# Tiny_5_Stick_PTH_-v2.net
KiCad netlist of a schematic drawn in EAGLE
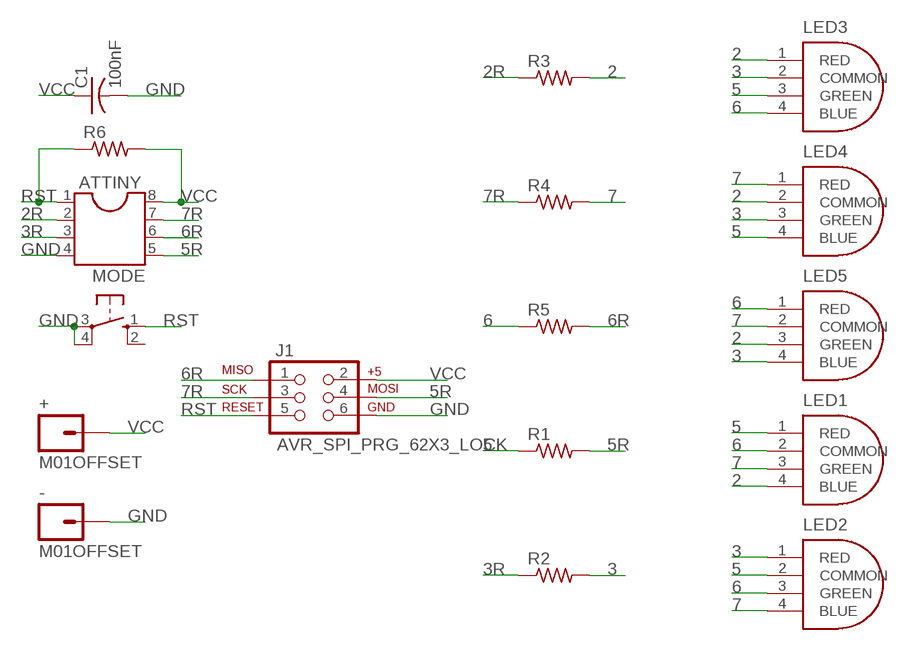
[diagram p0: schematic, sheet 1]

(export (version "E")
  (design (tool "Eeschema 10.0.6"))
  (components
    (comp (ref "+")
      (value "M01OFFSET")
      (footprint "eagle-import:1X01_OFFSET")
      (libsource (lib "eagle-import") (part "M01OFFSET"))
    )
    (comp (ref "-")
      (value "M01OFFSET")
      (footprint "eagle-import:1X01_OFFSET")
      (libsource (lib "eagle-import") (part "M01OFFSET"))
    )
    (comp (ref "ATTINY")
      (value "DIL8S")
      (footprint "eagle-import:SOCKET-08")
      (libsource (lib "eagle-import") (part "DIL8S"))
    )
    (comp (ref "C1")
      (value "100nF")
      (footprint "eagle-import:C025-025X050")
      (libsource (lib "eagle-import") (part "C-US025-025X050"))
    )
    (comp (ref "J1")
      (value "AVR_SPI_PRG_62X3_LOCK")
      (footprint "eagle-import:2X3_LOCK")
      (libsource (lib "eagle-import") (part "AVR_SPI_PRG_62X3_LOCK"))
    )
    (comp (ref "LED1")
      (value "10MM-RGB-LEDSEEED")
      (footprint "eagle-import:10MM-RGB-LED-SEEED-VALID")
      (libsource (lib "eagle-import") (part "10MM-RGB-LEDSEEED"))
    )
    (comp (ref "LED2")
      (value "10MM-RGB-LEDSEEED")
      (footprint "eagle-import:10MM-RGB-LED-SEEED-VALID")
      (libsource (lib "eagle-import") (part "10MM-RGB-LEDSEEED"))
    )
    (comp (ref "LED3")
      (value "10MM-RGB-LEDSEEED")
      (footprint "eagle-import:10MM-RGB-LED-SEEED-VALID")
      (libsource (lib "eagle-import") (part "10MM-RGB-LEDSEEED"))
    )
    (comp (ref "LED4")
      (value "10MM-RGB-LEDSEEED")
      (footprint "eagle-import:10MM-RGB-LED-SEEED-VALID")
      (libsource (lib "eagle-import") (part "10MM-RGB-LEDSEEED"))
    )
    (comp (ref "LED5")
      (value "10MM-RGB-LEDSEEED")
      (footprint "eagle-import:10MM-RGB-LED-SEEED-VALID")
      (libsource (lib "eagle-import") (part "10MM-RGB-LEDSEEED"))
    )
    (comp (ref "MODE")
      (value "10-XX")
      (footprint "eagle-import:B3F-10XX")
      (fields (field (name "MPN") "B3F-1000"))
      (libsource (lib "eagle-import") (part "10-XX"))
    )
    (comp (ref "R1")
      (value "R-US_0207/7")
      (footprint "eagle-import:0207_7")
      (libsource (lib "eagle-import") (part "R-US_0207/7"))
    )
    (comp (ref "R2")
      (value "R-US_0207/7")
      (footprint "eagle-import:0207_7")
      (libsource (lib "eagle-import") (part "R-US_0207/7"))
    )
    (comp (ref "R3")
      (value "R-US_0207/7")
      (footprint "eagle-import:0207_7")
      (libsource (lib "eagle-import") (part "R-US_0207/7"))
    )
    (comp (ref "R4")
      (value "R-US_0207/7")
      (footprint "eagle-import:0207_7")
      (libsource (lib "eagle-import") (part "R-US_0207/7"))
    )
    (comp (ref "R5")
      (value "R-US_0207/7")
      (footprint "eagle-import:0207_7")
      (libsource (lib "eagle-import") (part "R-US_0207/7"))
    )
    (comp (ref "R6")
      (value "R-US_0207/2V")
      (footprint "eagle-import:0207_2V")
      (libsource (lib "eagle-import") (part "R-US_0207/2V"))
    )
  )
  (nets
    (net (code "1") (name "/2") (class "Default")
      (node (ref "LED1") (pin "4") (pinfunction "BLUE_4") (pintype "bidirectional"))
      (node (ref "LED3") (pin "1") (pinfunction "RED_1") (pintype "bidirectional"))
      (node (ref "LED4") (pin "2") (pinfunction "COMMON_2") (pintype "bidirectional"))
      (node (ref "LED5") (pin "3") (pinfunction "GREEN_3") (pintype "bidirectional"))
      (node (ref "R3") (pin "2") (pinfunction "2_2") (pintype "passive"))
    )
    (net (code "2") (name "/2R") (class "Default")
      (node (ref "ATTINY") (pin "2") (pinfunction "2_2") (pintype "passive"))
      (node (ref "R3") (pin "1") (pinfunction "1_1") (pintype "passive"))
    )
    (net (code "3") (name "/3") (class "Default")
      (node (ref "LED2") (pin "1") (pinfunction "RED_1") (pintype "bidirectional"))
      (node (ref "LED3") (pin "2") (pinfunction "COMMON_2") (pintype "bidirectional"))
      (node (ref "LED4") (pin "3") (pinfunction "GREEN_3") (pintype "bidirectional"))
      (node (ref "LED5") (pin "4") (pinfunction "BLUE_4") (pintype "bidirectional"))
      (node (ref "R2") (pin "2") (pinfunction "2_2") (pintype "passive"))
    )
    (net (code "4") (name "/3R") (class "Default")
      (node (ref "ATTINY") (pin "3") (pinfunction "3_3") (pintype "passive"))
      (node (ref "R2") (pin "1") (pinfunction "1_1") (pintype "passive"))
    )
    (net (code "5") (name "/5") (class "Default")
      (node (ref "LED1") (pin "1") (pinfunction "RED_1") (pintype "bidirectional"))
      (node (ref "LED2") (pin "2") (pinfunction "COMMON_2") (pintype "bidirectional"))
      (node (ref "LED3") (pin "3") (pinfunction "GREEN_3") (pintype "bidirectional"))
      (node (ref "LED4") (pin "4") (pinfunction "BLUE_4") (pintype "bidirectional"))
      (node (ref "R1") (pin "1") (pinfunction "1_1") (pintype "passive"))
    )
    (net (code "6") (name "/5R") (class "Default")
      (node (ref "ATTINY") (pin "5") (pinfunction "5_5") (pintype "passive"))
      (node (ref "J1") (pin "4") (pinfunction "4_4") (pintype "passive"))
      (node (ref "R1") (pin "2") (pinfunction "2_2") (pintype "passive"))
    )
    (net (code "7") (name "/6") (class "Default")
      (node (ref "LED1") (pin "2") (pinfunction "COMMON_2") (pintype "bidirectional"))
      (node (ref "LED2") (pin "3") (pinfunction "GREEN_3") (pintype "bidirectional"))
      (node (ref "LED3") (pin "4") (pinfunction "BLUE_4") (pintype "bidirectional"))
      (node (ref "LED5") (pin "1") (pinfunction "RED_1") (pintype "bidirectional"))
      (node (ref "R5") (pin "1") (pinfunction "1_1") (pintype "passive"))
    )
    (net (code "8") (name "/6R") (class "Default")
      (node (ref "ATTINY") (pin "6") (pinfunction "6_6") (pintype "passive"))
      (node (ref "J1") (pin "1") (pinfunction "1_1") (pintype "passive"))
      (node (ref "R5") (pin "2") (pinfunction "2_2") (pintype "passive"))
    )
    (net (code "9") (name "/7") (class "Default")
      (node (ref "LED1") (pin "3") (pinfunction "GREEN_3") (pintype "bidirectional"))
      (node (ref "LED2") (pin "4") (pinfunction "BLUE_4") (pintype "bidirectional"))
      (node (ref "LED4") (pin "1") (pinfunction "RED_1") (pintype "bidirectional"))
      (node (ref "LED5") (pin "2") (pinfunction "COMMON_2") (pintype "bidirectional"))
      (node (ref "R4") (pin "2") (pinfunction "2_2") (pintype "passive"))
    )
    (net (code "10") (name "/7R") (class "Default")
      (node (ref "ATTINY") (pin "7") (pinfunction "7_7") (pintype "passive"))
      (node (ref "J1") (pin "3") (pinfunction "3_3") (pintype "passive"))
      (node (ref "R4") (pin "1") (pinfunction "1_1") (pintype "passive"))
    )
    (net (code "11") (name "/GND") (class "Default")
      (node (ref "-") (pin "1") (pinfunction "1_1") (pintype "passive"))
      (node (ref "ATTINY") (pin "4") (pinfunction "4_4") (pintype "passive"))
      (node (ref "C1") (pin "2") (pinfunction "2_2") (pintype "passive"))
      (node (ref "J1") (pin "6") (pinfunction "6_6") (pintype "passive"))
      (node (ref "MODE") (pin "3") (pinfunction "P_3") (pintype "passive"))
      (node (ref "MODE") (pin "4") (pinfunction "P1_4") (pintype "passive"))
    )
    (net (code "12") (name "/RST") (class "Default")
      (node (ref "ATTINY") (pin "1") (pinfunction "1_1") (pintype "passive"))
      (node (ref "J1") (pin "5") (pinfunction "5_5") (pintype "passive"))
      (node (ref "MODE") (pin "1") (pinfunction "S_1") (pintype "passive"))
      (node (ref "R6") (pin "1") (pinfunction "1_1") (pintype "passive"))
    )
    (net (code "13") (name "/VCC") (class "Default")
      (node (ref "+") (pin "1") (pinfunction "1_1") (pintype "passive"))
      (node (ref "ATTINY") (pin "8") (pinfunction "8_8") (pintype "passive"))
      (node (ref "C1") (pin "1") (pinfunction "1_1") (pintype "passive"))
      (node (ref "J1") (pin "2") (pinfunction "2_2") (pintype "passive"))
      (node (ref "R6") (pin "2") (pinfunction "2_2") (pintype "passive"))
    )
    (net (code "14") (name "unconnected-(MODE-S1-Pad2)") (class "Default")
      (node (ref "MODE") (pin "2") (pinfunction "S1_2") (pintype "passive"))
    )
  )
)
